# IBVG-DRIVER.net
KiCad netlist of a schematic drawn in Altium Designer
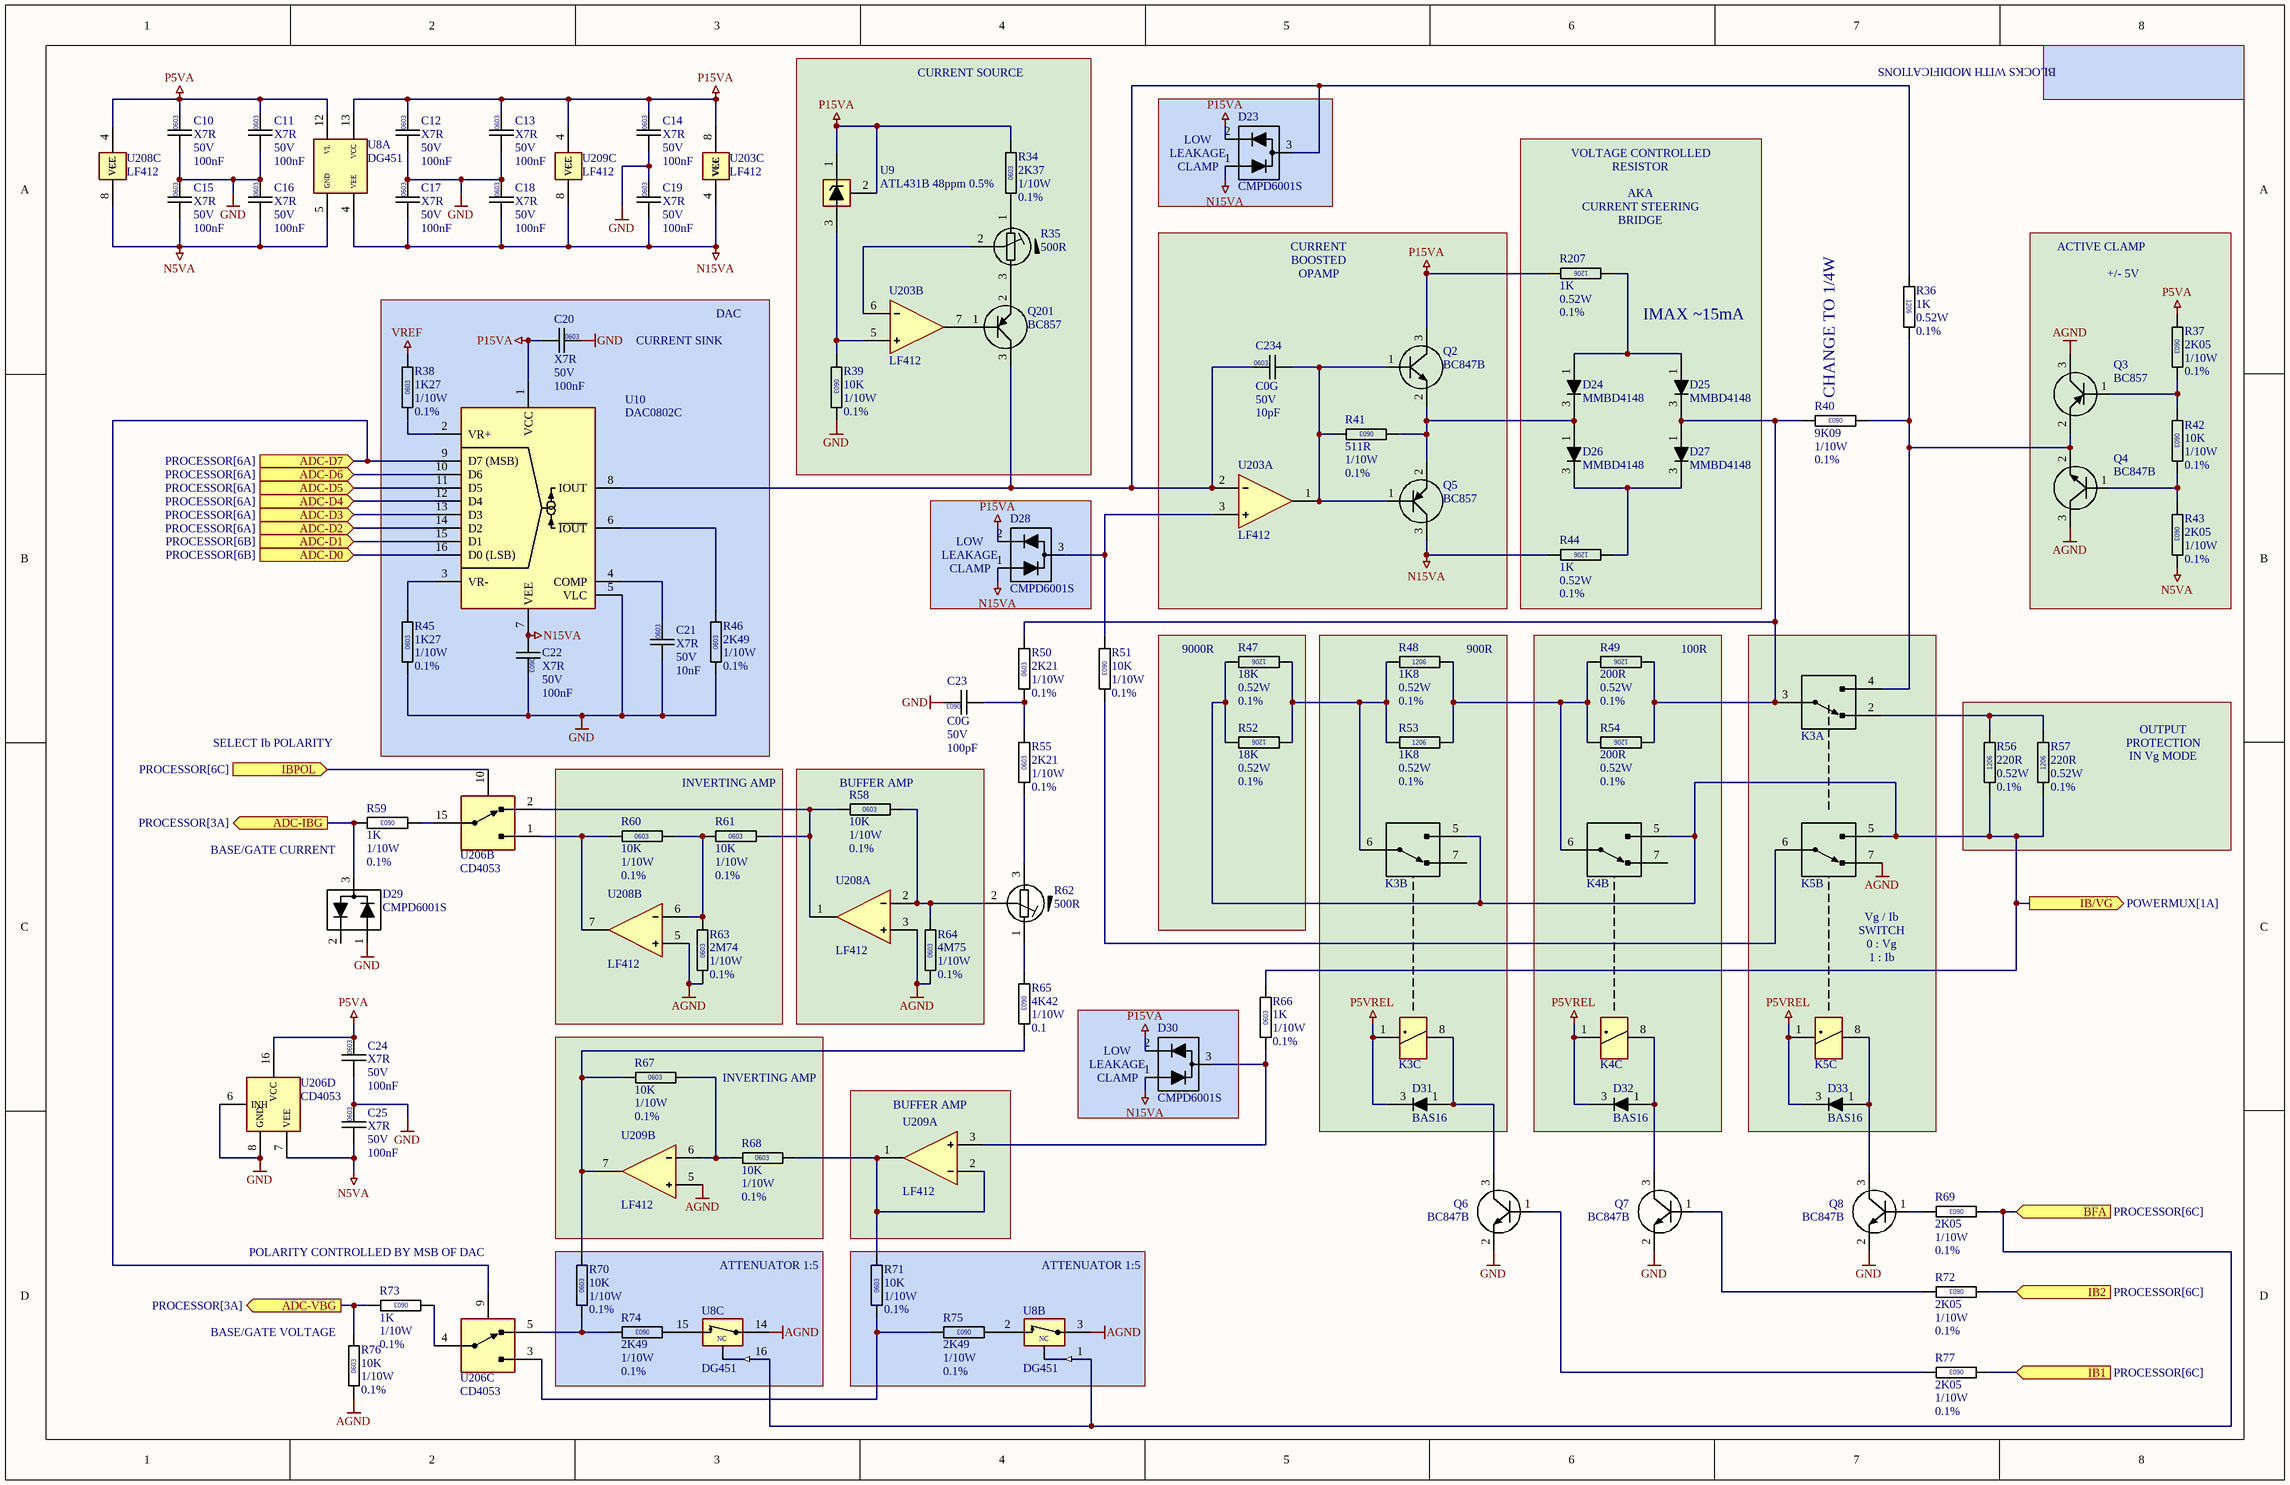
[diagram p0: IBVG-DRIVER.SchDoc]

(export (version "E")
  (design (tool "Eeschema 10.0.6"))
  (components
    (comp (ref "C10")
      (value "CAP0603")
      (footprint "CAPC0603")
      (description "CAPACITOR,CERAMIC,100nF,50V,X7R,0603")
      (fields
        (field (name "DIELECTRIC") "X7R")
        (field (name "VOLTAGE") "50V")
        (field (name "CAPACITANCE") "100nF")
      )
      (libsource (lib "CAPACITORS") (part "CAPC-0603-100nF-50V-X7R"))
    )
    (comp (ref "C11")
      (value "CAP0603")
      (footprint "CAPC0603")
      (description "CAPACITOR,CERAMIC,100nF,50V,X7R,0603")
      (fields
        (field (name "DIELECTRIC") "X7R")
        (field (name "VOLTAGE") "50V")
        (field (name "CAPACITANCE") "100nF")
      )
      (libsource (lib "CAPACITORS") (part "CAPC-0603-100nF-50V-X7R"))
    )
    (comp (ref "C12")
      (value "CAP0603")
      (footprint "CAPC0603")
      (description "CAPACITOR,CERAMIC,100nF,50V,X7R,0603")
      (fields
        (field (name "DIELECTRIC") "X7R")
        (field (name "VOLTAGE") "50V")
        (field (name "CAPACITANCE") "100nF")
      )
      (libsource (lib "CAPACITORS") (part "CAPC-0603-100nF-50V-X7R"))
    )
    (comp (ref "C13")
      (value "CAP0603")
      (footprint "CAPC0603")
      (description "CAPACITOR,CERAMIC,100nF,50V,X7R,0603")
      (fields
        (field (name "DIELECTRIC") "X7R")
        (field (name "VOLTAGE") "50V")
        (field (name "CAPACITANCE") "100nF")
      )
      (libsource (lib "CAPACITORS") (part "CAPC-0603-100nF-50V-X7R"))
    )
    (comp (ref "C14")
      (value "CAP0603")
      (footprint "CAPC0603")
      (description "CAPACITOR,CERAMIC,100nF,50V,X7R,0603")
      (fields
        (field (name "DIELECTRIC") "X7R")
        (field (name "VOLTAGE") "50V")
        (field (name "CAPACITANCE") "100nF")
      )
      (libsource (lib "CAPACITORS") (part "CAPC-0603-100nF-50V-X7R"))
    )
    (comp (ref "C15")
      (value "CAP0603")
      (footprint "CAPC0603")
      (description "CAPACITOR,CERAMIC,100nF,50V,X7R,0603")
      (fields
        (field (name "DIELECTRIC") "X7R")
        (field (name "VOLTAGE") "50V")
        (field (name "CAPACITANCE") "100nF")
      )
      (libsource (lib "CAPACITORS") (part "CAPC-0603-100nF-50V-X7R"))
    )
    (comp (ref "C16")
      (value "CAP0603")
      (footprint "CAPC0603")
      (description "CAPACITOR,CERAMIC,100nF,50V,X7R,0603")
      (fields
        (field (name "DIELECTRIC") "X7R")
        (field (name "VOLTAGE") "50V")
        (field (name "CAPACITANCE") "100nF")
      )
      (libsource (lib "CAPACITORS") (part "CAPC-0603-100nF-50V-X7R"))
    )
    (comp (ref "C17")
      (value "CAP0603")
      (footprint "CAPC0603")
      (description "CAPACITOR,CERAMIC,100nF,50V,X7R,0603")
      (fields
        (field (name "DIELECTRIC") "X7R")
        (field (name "VOLTAGE") "50V")
        (field (name "CAPACITANCE") "100nF")
      )
      (libsource (lib "CAPACITORS") (part "CAPC-0603-100nF-50V-X7R"))
    )
    (comp (ref "C18")
      (value "CAP0603")
      (footprint "CAPC0603")
      (description "CAPACITOR,CERAMIC,100nF,50V,X7R,0603")
      (fields
        (field (name "DIELECTRIC") "X7R")
        (field (name "VOLTAGE") "50V")
        (field (name "CAPACITANCE") "100nF")
      )
      (libsource (lib "CAPACITORS") (part "CAPC-0603-100nF-50V-X7R"))
    )
    (comp (ref "C19")
      (value "CAP0603")
      (footprint "CAPC0603")
      (description "CAPACITOR,CERAMIC,100nF,50V,X7R,0603")
      (fields
        (field (name "DIELECTRIC") "X7R")
        (field (name "VOLTAGE") "50V")
        (field (name "CAPACITANCE") "100nF")
      )
      (libsource (lib "CAPACITORS") (part "CAPC-0603-100nF-50V-X7R"))
    )
    (comp (ref "C20")
      (value "CAP0603")
      (footprint "CAPC0603")
      (description "CAPACITOR,CERAMIC,100nF,50V,X7R,0603")
      (fields
        (field (name "DIELECTRIC") "X7R")
        (field (name "VOLTAGE") "50V")
        (field (name "CAPACITANCE") "100nF")
      )
      (libsource (lib "CAPACITORS") (part "CAPC-0603-100nF-50V-X7R"))
    )
    (comp (ref "C21")
      (value "CAP0603")
      (footprint "CAPC0603")
      (description "CAPACITOR,CERAMIC,10nF,50V,X7R,0603")
      (fields
        (field (name "DIELECTRIC") "X7R")
        (field (name "VOLTAGE") "50V")
        (field (name "CAPACITANCE") "10nF")
      )
      (libsource (lib "CAPACITORS") (part "CAPC-0603-10nF-50V-X7R"))
    )
    (comp (ref "C22")
      (value "CAP0603")
      (footprint "CAPC0603")
      (description "CAPACITOR,CERAMIC,100nF,50V,X7R,0603")
      (fields
        (field (name "DIELECTRIC") "X7R")
        (field (name "VOLTAGE") "50V")
        (field (name "CAPACITANCE") "100nF")
      )
      (libsource (lib "CAPACITORS") (part "CAPC-0603-100nF-50V-X7R"))
    )
    (comp (ref "C23")
      (value "CAP0603")
      (footprint "CAPC0603")
      (description "CAPACITOR,CERAMIC,100pF,50V,C0G,0603")
      (fields
        (field (name "DIELECTRIC") "C0G")
        (field (name "VOLTAGE") "50V")
        (field (name "CAPACITANCE") "100pF")
      )
      (libsource (lib "CAPACITORS") (part "CAPC-0603-100pF-50V-C0G"))
    )
    (comp (ref "C24")
      (value "CAP0603")
      (footprint "CAPC0603")
      (description "CAPACITOR,CERAMIC,100nF,50V,X7R,0603")
      (fields
        (field (name "DIELECTRIC") "X7R")
        (field (name "VOLTAGE") "50V")
        (field (name "CAPACITANCE") "100nF")
      )
      (libsource (lib "CAPACITORS") (part "CAPC-0603-100nF-50V-X7R"))
    )
    (comp (ref "C25")
      (value "CAP0603")
      (footprint "CAPC0603")
      (description "CAPACITOR,CERAMIC,100nF,50V,X7R,0603")
      (fields
        (field (name "DIELECTRIC") "X7R")
        (field (name "VOLTAGE") "50V")
        (field (name "CAPACITANCE") "100nF")
      )
      (libsource (lib "CAPACITORS") (part "CAPC-0603-100nF-50V-X7R"))
    )
    (comp (ref "C234")
      (value "CAP0603")
      (footprint "CAPC0603")
      (description "CAPACITOR,CERAMIC,10pF,50V,C0G,0603")
      (fields
        (field (name "DIELECTRIC") "C0G")
        (field (name "VOLTAGE") "50V")
        (field (name "CAPACITANCE") "10pF")
      )
      (libsource (lib "CAPACITORS") (part "CAPC-0603-10PF-50V-C0G"))
    )
    (comp (ref "D23")
      (value "CMPD6001S")
      (footprint "SOT23")
      (description "DIODE,75V,250mA,SOT23,500pA ULTRA LOW LEAKAGE")
      (libsource (lib "DIODES") (part "DIODE-CENTRALSEMI-CMPD6001S"))
    )
    (comp (ref "D24")
      (value "MMBD4148")
      (description "DIODE,RECTIFIER,75V,0.3A,MMBD4148,SOT23")
      (libsource (lib "DIODES") (part "DIODE-RECTIFIER-DIODES-MMBD4148-SOT23"))
    )
    (comp (ref "D25")
      (value "MMBD4148")
      (description "DIODE,RECTIFIER,75V,0.3A,MMBD4148,SOT23")
      (libsource (lib "DIODES") (part "DIODE-RECTIFIER-DIODES-MMBD4148-SOT23"))
    )
    (comp (ref "D26")
      (value "MMBD4148")
      (description "DIODE,RECTIFIER,75V,0.3A,MMBD4148,SOT23")
      (libsource (lib "DIODES") (part "DIODE-RECTIFIER-DIODES-MMBD4148-SOT23"))
    )
    (comp (ref "D27")
      (value "MMBD4148")
      (description "DIODE,RECTIFIER,75V,0.3A,MMBD4148,SOT23")
      (libsource (lib "DIODES") (part "DIODE-RECTIFIER-DIODES-MMBD4148-SOT23"))
    )
    (comp (ref "D28")
      (value "CMPD6001S")
      (footprint "SOT23")
      (description "DIODE,75V,250mA,SOT23,500pA ULTRA LOW LEAKAGE")
      (libsource (lib "DIODES") (part "DIODE-CENTRALSEMI-CMPD6001S"))
    )
    (comp (ref "D29")
      (value "CMPD6001S")
      (footprint "SOT23")
      (description "DIODE,75V,250mA,SOT23,500pA ULTRA LOW LEAKAGE")
      (libsource (lib "DIODES") (part "DIODE-CENTRALSEMI-CMPD6001S"))
    )
    (comp (ref "D30")
      (value "CMPD6001S")
      (footprint "SOT23")
      (description "DIODE,75V,250mA,SOT23,500pA ULTRA LOW LEAKAGE")
      (libsource (lib "DIODES") (part "DIODE-CENTRALSEMI-CMPD6001S"))
    )
    (comp (ref "D31")
      (value "BAS16")
      (footprint "SOT23")
      (description "DIODE,RECTIFIER,75V,0.3A,BAS16,SOT23")
      (libsource (lib "DIODES") (part "DIODE-RECTIFIER-DIODES-BAS16-SOT23"))
    )
    (comp (ref "D32")
      (value "BAS16")
      (footprint "SOT23")
      (description "DIODE,RECTIFIER,75V,0.3A,BAS16,SOT23")
      (libsource (lib "DIODES") (part "DIODE-RECTIFIER-DIODES-BAS16-SOT23"))
    )
    (comp (ref "D33")
      (value "BAS16")
      (footprint "SOT23")
      (description "DIODE,RECTIFIER,75V,0.3A,BAS16,SOT23")
      (libsource (lib "DIODES") (part "DIODE-RECTIFIER-DIODES-BAS16-SOT23"))
    )
    (comp (ref "K3")
      (value "RELAY-KEMET-UA2-5NJ")
      (footprint "RELAY-KEMET-UA2-5NJ")
      (description "RELAY,DPDT,1A,250VAC,220VDC,5V COIL,KEMET,UA2-5NJ")
      (libsource (lib "") (part "RELAY-KEMET-UA2-5NJ_1"))
    )
    (comp (ref "K4")
      (value "RELAY-KEMET-UA2-5NJ")
      (footprint "RELAY-KEMET-UA2-5NJ")
      (description "RELAY,DPDT,1A,250VAC,220VDC,5V COIL,KEMET,UA2-5NJ")
      (libsource (lib "RELAYS") (part "RELAY-KEMET-UA2-5NJ"))
    )
    (comp (ref "K5")
      (value "RELAY-KEMET-UA2-5NJ")
      (footprint "RELAY-KEMET-UA2-5NJ")
      (description "RELAY,DPDT,1A,250VAC,220VDC,5V COIL,KEMET,UA2-5NJ")
      (libsource (lib "RELAYS") (part "RELAY-KEMET-UA2-5NJ"))
    )
    (comp (ref "Q2")
      (value "BC847B")
      (footprint "SOT23")
      (description "XSTR,NPN,45V,0.1A,,BC847B,SOT23")
      (libsource (lib "TRANSISTORS") (part "XSTR-NPN-BC847"))
    )
    (comp (ref "Q3")
      (value "BC857")
      (footprint "SOT23")
      (description "XSTR,PNP,SOT23,BC857,SOT23")
      (libsource (lib "TRANSISTORS") (part "XSTR-PNP-BC857"))
    )
    (comp (ref "Q4")
      (value "BC847B")
      (footprint "SOT23")
      (description "XSTR,NPN,45V,0.1A,,BC847B,SOT23")
      (libsource (lib "TRANSISTORS") (part "XSTR-NPN-BC847"))
    )
    (comp (ref "Q5")
      (value "BC857")
      (footprint "SOT23")
      (description "XSTR,PNP,SOT23,BC857,SOT23")
      (libsource (lib "TRANSISTORS") (part "XSTR-PNP-BC857"))
    )
    (comp (ref "Q6")
      (value "BC847B")
      (footprint "SOT23")
      (description "XSTR,NPN,45V,0.1A,,BC847B,SOT23")
      (libsource (lib "TRANSISTORS") (part "XSTR-NPN-BC847"))
    )
    (comp (ref "Q7")
      (value "BC847B")
      (footprint "SOT23")
      (description "XSTR,NPN,45V,0.1A,,BC847B,SOT23")
      (libsource (lib "TRANSISTORS") (part "XSTR-NPN-BC847"))
    )
    (comp (ref "Q8")
      (value "BC847B")
      (footprint "SOT23")
      (description "XSTR,NPN,45V,0.1A,,BC847B,SOT23")
      (libsource (lib "TRANSISTORS") (part "XSTR-NPN-BC847"))
    )
    (comp (ref "Q201")
      (value "BC857")
      (footprint "SOT23")
      (description "XSTR,PNP,SOT23,BC857,SOT23")
      (libsource (lib "TRANSISTORS") (part "XSTR-PNP-BC857"))
    )
    (comp (ref "R34")
      (value "2K37")
      (footprint "RESC0603")
      (description "RESISTOR,2K37,0.1%,100mW,0603 (1608)")
      (fields
        (field (name "POWER") "1/10W")
        (field (name "TOLERANCE") "0.1%")
        (field (name "Comment") "RESC0603")
      )
      (libsource (lib "RESISTORS") (part "RESC-0603-2K37-0.1%-1/10W"))
    )
    (comp (ref "R35")
      (value "500R")
      (footprint "TRIMMER-BOURNS-3214X")
      (description "RESISTOR,MULTITURN,VERTICAL,5T,500R")
      (fields (field (name "Comment") "TRIMMER-BOURNS-3214X-1-501"))
      (libsource (lib "RESISTORS") (part "TRIMMER-BOURNS-3214X-1-501"))
    )
    (comp (ref "R36")
      (value "1K")
      (footprint "RESC1206")
      (description "RESISTOR,1K,1206,0.1%,520mW,1206")
      (fields
        (field (name "POWER") "0.52W")
        (field (name "TOLERANCE") "0.1%")
        (field (name "Comment") "RESC1206")
      )
      (libsource (lib "RESISTORS") (part "RESC-1206-1K-0.1%-1/2W"))
    )
    (comp (ref "R37")
      (value "2K05")
      (footprint "RESC0603")
      (description "RESISTOR,2K05,0.11%,100mW,0603 (1608)")
      (fields
        (field (name "POWER") "1/10W")
        (field (name "TOLERANCE") "0.1%")
        (field (name "Comment") "RESC0603")
      )
      (libsource (lib "RESISTORS") (part "RESC-0603-2K05-0.1%-1/10W"))
    )
    (comp (ref "R38")
      (value "1K27")
      (footprint "RESC0603")
      (description "RESISTOR,1K27,0.1%,100mW,0603 (1608)")
      (fields
        (field (name "POWER") "1/10W")
        (field (name "TOLERANCE") "0.1%")
        (field (name "Comment") "RESC0603")
      )
      (libsource (lib "RESISTORS") (part "RESC-0603-1K27-0.1%-1/10W"))
    )
    (comp (ref "R39")
      (value "10K")
      (footprint "RESC0603")
      (description "RESISTOR,10K,0.1%,100mW,0603 (1608)")
      (fields
        (field (name "POWER") "1/10W")
        (field (name "TOLERANCE") "0.1%")
        (field (name "Comment") "RESC0603")
      )
      (libsource (lib "RESISTORS") (part "RESC-0603-10K-0.1%-1/10W"))
    )
    (comp (ref "R40")
      (value "9K09")
      (footprint "RESC0603")
      (description "RESISTOR,9K09,0.1%,100mW,0603 (1608)")
      (fields
        (field (name "POWER") "1/10W")
        (field (name "TOLERANCE") "0.1%")
        (field (name "Comment") "RESC0603")
      )
      (libsource (lib "RESISTORS") (part "RESC-0603-9K09-0.1%-1/10W"))
    )
    (comp (ref "R41")
      (value "511R")
      (footprint "RESC0603")
      (description "RESISTOR,511R,0.1%,100mW,0603 (1608)")
      (fields
        (field (name "POWER") "1/10W")
        (field (name "TOLERANCE") "0.1%")
        (field (name "Comment") "RESC0603")
      )
      (libsource (lib "RESISTORS") (part "RESC-0603-511R-0.1%-1/10W"))
    )
    (comp (ref "R42")
      (value "10K")
      (footprint "RESC0603")
      (description "RESISTOR,10K,0.1%,100mW,0603 (1608)")
      (fields
        (field (name "POWER") "1/10W")
        (field (name "TOLERANCE") "0.1%")
        (field (name "Comment") "RESC0603")
      )
      (libsource (lib "RESISTORS") (part "RESC-0603-10K-0.1%-1/10W"))
    )
    (comp (ref "R43")
      (value "2K05")
      (footprint "RESC0603")
      (description "RESISTOR,2K05,0.11%,100mW,0603 (1608)")
      (fields
        (field (name "POWER") "1/10W")
        (field (name "TOLERANCE") "0.1%")
        (field (name "Comment") "RESC0603")
      )
      (libsource (lib "RESISTORS") (part "RESC-0603-2K05-0.1%-1/10W"))
    )
    (comp (ref "R44")
      (value "1K")
      (footprint "RESC1206")
      (description "RESISTOR,1K,1206,0.1%,520mW,1206")
      (fields
        (field (name "POWER") "0.52W")
        (field (name "TOLERANCE") "0.1%")
        (field (name "Comment") "RESC1206")
      )
      (libsource (lib "RESISTORS") (part "RESC-1206-1K-0.1%-1/2W"))
    )
    (comp (ref "R45")
      (value "1K27")
      (footprint "RESC0603")
      (description "RESISTOR,1K27,0.1%,100mW,0603 (1608)")
      (fields
        (field (name "POWER") "1/10W")
        (field (name "TOLERANCE") "0.1%")
        (field (name "Comment") "RESC0603")
      )
      (libsource (lib "RESISTORS") (part "RESC-0603-1K27-0.1%-1/10W"))
    )
    (comp (ref "R46")
      (value "2K49")
      (footprint "RESC0603")
      (description "RESISTOR,2K49,0.1%,100mW,0603 (1608)")
      (fields
        (field (name "POWER") "1/10W")
        (field (name "TOLERANCE") "0.1%")
        (field (name "Comment") "RESC0603")
      )
      (libsource (lib "RESISTORS") (part "RESC-0603-2K49-0.1%-1/10W"))
    )
    (comp (ref "R47")
      (value "18K")
      (footprint "RESC1206")
      (description "RESISTOR,18K,1206,0.1%,520mW,1206")
      (fields
        (field (name "POWER") "0.52W")
        (field (name "TOLERANCE") "0.1%")
        (field (name "Comment") "RESC1206")
      )
      (libsource (lib "RESISTORS") (part "RESC-1206-18K-0.1%-1/2W"))
    )
    (comp (ref "R48")
      (value "1K8")
      (footprint "RESC1206")
      (description "RESISTOR,1K8,1206,0.1%,520mW,1206")
      (fields
        (field (name "POWER") "0.52W")
        (field (name "TOLERANCE") "0.1%")
        (field (name "Comment") "RESC1206")
      )
      (libsource (lib "RESISTORS") (part "RESC-1206-1K8-0.1%-1/2W"))
    )
    (comp (ref "R49")
      (value "200R")
      (footprint "RESC1206")
      (description "RESISTOR,200R,1206,0.1%,520mW,1206")
      (fields
        (field (name "POWER") "0.52W")
        (field (name "TOLERANCE") "0.1%")
        (field (name "Comment") "RESC1206")
      )
      (libsource (lib "RESISTORS") (part "RESC-1206-200R-0.1%-1/2W"))
    )
    (comp (ref "R50")
      (value "2K21")
      (footprint "RESC0603")
      (description "RESISTOR,2K21,0.1%,100mW,0603 (1608)")
      (fields
        (field (name "POWER") "1/10W")
        (field (name "TOLERANCE") "0.1%")
        (field (name "Comment") "RESC0603")
      )
      (libsource (lib "RESISTORS") (part "RESC-0603-2K21-0.1%-1/10W"))
    )
    (comp (ref "R51")
      (value "10K")
      (footprint "RESC0603")
      (description "RESISTOR,10K,0.1%,100mW,0603 (1608)")
      (fields
        (field (name "POWER") "1/10W")
        (field (name "TOLERANCE") "0.1%")
        (field (name "Comment") "RESC0603")
      )
      (libsource (lib "RESISTORS") (part "RESC-0603-10K-0.1%-1/10W"))
    )
    (comp (ref "R52")
      (value "18K")
      (footprint "RESC1206")
      (description "RESISTOR,18K,1206,0.1%,520mW,1206")
      (fields
        (field (name "POWER") "0.52W")
        (field (name "TOLERANCE") "0.1%")
        (field (name "Comment") "RESC1206")
      )
      (libsource (lib "RESISTORS") (part "RESC-1206-18K-0.1%-1/2W"))
    )
    (comp (ref "R53")
      (value "1K8")
      (footprint "RESC1206")
      (description "RESISTOR,1K8,1206,0.1%,520mW,1206")
      (fields
        (field (name "POWER") "0.52W")
        (field (name "TOLERANCE") "0.1%")
        (field (name "Comment") "RESC1206")
      )
      (libsource (lib "RESISTORS") (part "RESC-1206-1K8-0.1%-1/2W"))
    )
    (comp (ref "R54")
      (value "200R")
      (footprint "RESC1206")
      (description "RESISTOR,200R,1206,0.1%,520mW,1206")
      (fields
        (field (name "POWER") "0.52W")
        (field (name "TOLERANCE") "0.1%")
        (field (name "Comment") "RESC1206")
      )
      (libsource (lib "RESISTORS") (part "RESC-1206-200R-0.1%-1/2W"))
    )
    (comp (ref "R55")
      (value "2K21")
      (footprint "RESC0603")
      (description "RESISTOR,2K21,0.1%,100mW,0603 (1608)")
      (fields
        (field (name "POWER") "1/10W")
        (field (name "TOLERANCE") "0.1%")
        (field (name "Comment") "RESC0603")
      )
      (libsource (lib "RESISTORS") (part "RESC-0603-2K21-0.1%-1/10W"))
    )
    (comp (ref "R56")
      (value "220R")
      (footprint "RESC1206")
      (description "RESISTOR,220R,1206,0.1%,520mW,1206")
      (fields
        (field (name "POWER") "0.52W")
        (field (name "TOLERANCE") "0.1%")
        (field (name "Comment") "RESC1206")
      )
      (libsource (lib "RESISTORS") (part "RESC-1206-220R-0.1%-1/2W"))
    )
    (comp (ref "R57")
      (value "220R")
      (footprint "RESC1206")
      (description "RESISTOR,220R,1206,0.1%,520mW,1206")
      (fields
        (field (name "POWER") "0.52W")
        (field (name "TOLERANCE") "0.1%")
        (field (name "Comment") "RESC1206")
      )
      (libsource (lib "RESISTORS") (part "RESC-1206-220R-0.1%-1/2W"))
    )
    (comp (ref "R58")
      (value "10K")
      (footprint "RESC0603")
      (description "RESISTOR,10K,0.1%,100mW,0603 (1608)")
      (fields
        (field (name "POWER") "1/10W")
        (field (name "TOLERANCE") "0.1%")
        (field (name "Comment") "RESC0603")
      )
      (libsource (lib "RESISTORS") (part "RESC-0603-10K-0.1%-1/10W"))
    )
    (comp (ref "R59")
      (value "1K")
      (footprint "RESC0603")
      (description "RESISTOR,1K,0.1%,100mW,0603 (1608)")
      (fields
        (field (name "POWER") "1/10W")
        (field (name "TOLERANCE") "0.1%")
        (field (name "Comment") "RESC0603")
      )
      (libsource (lib "RESISTORS") (part "RESC-0603-1K-0.1%-1/10W"))
    )
    (comp (ref "R60")
      (value "10K")
      (footprint "RESC0603")
      (description "RESISTOR,10K,0.1%,100mW,0603 (1608)")
      (fields
        (field (name "POWER") "1/10W")
        (field (name "TOLERANCE") "0.1%")
        (field (name "Comment") "RESC0603")
      )
      (libsource (lib "RESISTORS") (part "RESC-0603-10K-0.1%-1/10W"))
    )
    (comp (ref "R61")
      (value "10K")
      (footprint "RESC0603")
      (description "RESISTOR,10K,0.1%,100mW,0603 (1608)")
      (fields
        (field (name "POWER") "1/10W")
        (field (name "TOLERANCE") "0.1%")
        (field (name "Comment") "RESC0603")
      )
      (libsource (lib "RESISTORS") (part "RESC-0603-10K-0.1%-1/10W"))
    )
    (comp (ref "R62")
      (value "500R")
      (footprint "TRIMMER-BOURNS-3214X")
      (description "RESISTOR,MULTITURN,VERTICAL,5T,500R")
      (fields (field (name "Comment") "TRIMMER-BOURNS-3214X-1-501"))
      (libsource (lib "RESISTORS") (part "TRIMMER-BOURNS-3214X-1-501"))
    )
    (comp (ref "R63")
      (value "2M74")
      (footprint "RESC0603")
      (description "RESISTOR,2M74,0.1%,100mW,0603 (1608)")
      (fields
        (field (name "POWER") "1/10W")
        (field (name "TOLERANCE") "0.1%")
        (field (name "Comment") "RESC0603")
      )
      (libsource (lib "RESISTORS") (part "RESC-0603-2M74-0.1%-1/10W"))
    )
    (comp (ref "R64")
      (value "4M75")
      (footprint "RESC0603")
      (description "RESISTOR,4M75,0.1%,100mW,0603 (1608)")
      (fields
        (field (name "POWER") "1/10W")
        (field (name "TOLERANCE") "0.1%")
        (field (name "Comment") "RESC0603")
      )
      (libsource (lib "RESISTORS") (part "RESC-0603-4M75-1%-1/10W"))
    )
    (comp (ref "R65")
      (value "4K42")
      (footprint "RESC0603")
      (description "RESISTOR,4K42,0.1%,100mW,0603 (1608)")
      (fields
        (field (name "POWER") "1/10W")
        (field (name "TOLERANCE") "0.1")
        (field (name "Comment") "RESC0603")
      )
      (libsource (lib "RESISTORS") (part "RESC-0603-4K42-0.1%-1/10W"))
    )
    (comp (ref "R66")
      (value "1K")
      (footprint "RESC0603")
      (description "RESISTOR,1K,0.1%,100mW,0603 (1608)")
      (fields
        (field (name "POWER") "1/10W")
        (field (name "TOLERANCE") "0.1%")
        (field (name "Comment") "RESC0603")
      )
      (libsource (lib "RESISTORS") (part "RESC-0603-1K-0.1%-1/10W"))
    )
    (comp (ref "R67")
      (value "10K")
      (footprint "RESC0603")
      (description "RESISTOR,10K,0.1%,100mW,0603 (1608)")
      (fields
        (field (name "POWER") "1/10W")
        (field (name "TOLERANCE") "0.1%")
        (field (name "Comment") "RESC0603")
      )
      (libsource (lib "RESISTORS") (part "RESC-0603-10K-0.1%-1/10W"))
    )
    (comp (ref "R68")
      (value "10K")
      (footprint "RESC0603")
      (description "RESISTOR,10K,0.1%,100mW,0603 (1608)")
      (fields
        (field (name "POWER") "1/10W")
        (field (name "TOLERANCE") "0.1%")
        (field (name "Comment") "RESC0603")
      )
      (libsource (lib "RESISTORS") (part "RESC-0603-10K-0.1%-1/10W"))
    )
    (comp (ref "R69")
      (value "2K05")
      (footprint "RESC0603")
      (description "RESISTOR,2K05,0.11%,100mW,0603 (1608)")
      (fields
        (field (name "POWER") "1/10W")
        (field (name "TOLERANCE") "0.1%")
        (field (name "Comment") "RESC0603")
      )
      (libsource (lib "RESISTORS") (part "RESC-0603-2K05-0.1%-1/10W"))
    )
    (comp (ref "R70")
      (value "10K")
      (footprint "RESC0603")
      (description "RESISTOR,10K,0.1%,100mW,0603 (1608)")
      (fields
        (field (name "POWER") "1/10W")
        (field (name "TOLERANCE") "0.1%")
        (field (name "Comment") "RESC0603")
      )
      (libsource (lib "RESISTORS") (part "RESC-0603-10K-0.1%-1/10W"))
    )
    (comp (ref "R71")
      (value "10K")
      (footprint "RESC0603")
      (description "RESISTOR,10K,0.1%,100mW,0603 (1608)")
      (fields
        (field (name "POWER") "1/10W")
        (field (name "TOLERANCE") "0.1%")
        (field (name "Comment") "RESC0603")
      )
      (libsource (lib "RESISTORS") (part "RESC-0603-10K-0.1%-1/10W"))
    )
    (comp (ref "R72")
      (value "2K05")
      (footprint "RESC0603")
      (description "RESISTOR,2K05,0.11%,100mW,0603 (1608)")
      (fields
        (field (name "POWER") "1/10W")
        (field (name "TOLERANCE") "0.1%")
        (field (name "Comment") "RESC0603")
      )
      (libsource (lib "RESISTORS") (part "RESC-0603-2K05-0.1%-1/10W"))
    )
    (comp (ref "R73")
      (value "1K")
      (footprint "RESC0603")
      (description "RESISTOR,1K,0.1%,100mW,0603 (1608)")
      (fields
        (field (name "POWER") "1/10W")
        (field (name "TOLERANCE") "0.1%")
        (field (name "Comment") "RESC0603")
      )
      (libsource (lib "RESISTORS") (part "RESC-0603-1K-0.1%-1/10W"))
    )
    (comp (ref "R74")
      (value "2K49")
      (footprint "RESC0603")
      (description "RESISTOR,2K49,0.1%,100mW,0603 (1608)")
      (fields
        (field (name "POWER") "1/10W")
        (field (name "TOLERANCE") "0.1%")
        (field (name "Comment") "RESC0603")
      )
      (libsource (lib "RESISTORS") (part "RESC-0603-2K49-0.1%-1/10W"))
    )
    (comp (ref "R75")
      (value "2K49")
      (footprint "RESC0603")
      (description "RESISTOR,2K49,0.1%,100mW,0603 (1608)")
      (fields
        (field (name "POWER") "1/10W")
        (field (name "TOLERANCE") "0.1%")
        (field (name "Comment") "RESC0603")
      )
      (libsource (lib "RESISTORS") (part "RESC-0603-2K49-0.1%-1/10W"))
    )
    (comp (ref "R76")
      (value "10K")
      (footprint "RESC0603")
      (description "RESISTOR,10K,0.1%,100mW,0603 (1608)")
      (fields
        (field (name "POWER") "1/10W")
        (field (name "TOLERANCE") "0.1%")
        (field (name "Comment") "RESC0603")
      )
      (libsource (lib "RESISTORS") (part "RESC-0603-10K-0.1%-1/10W"))
    )
    (comp (ref "R77")
      (value "2K05")
      (footprint "RESC0603")
      (description "RESISTOR,2K05,0.11%,100mW,0603 (1608)")
      (fields
        (field (name "POWER") "1/10W")
        (field (name "TOLERANCE") "0.1%")
        (field (name "Comment") "RESC0603")
      )
      (libsource (lib "RESISTORS") (part "RESC-0603-2K05-0.1%-1/10W"))
    )
    (comp (ref "R207")
      (value "1K")
      (footprint "RESC1206")
      (description "RESISTOR,1K,1206,0.1%,520mW,1206")
      (fields
        (field (name "POWER") "0.52W")
        (field (name "TOLERANCE") "0.1%")
        (field (name "Comment") "RESC1206")
      )
      (libsource (lib "RESISTORS") (part "RESC-1206-1K-0.1%-1/2W"))
    )
    (comp (ref "U8")
      (value "DG451")
      (footprint "SO127P600-16N")
      (description "IC,ANALOG,4XSPST ANALOG SWITCH,NC,,SILICONIX,DG451,SO16")
      (libsource (lib "IC-ANALOG") (part "IC-SILICONIX-DG451"))
    )
    (comp (ref "U9")
      (value "ATL431B 48ppm 0.5%")
      (footprint "SOT23")
      (description "IC,REGULATOR,REFERENCE,SHUNT,0.5%,48ppm,TL431,SOT23")
      (libsource (lib "IC-ANALOG") (part "IC-TI-ATL431B-SOT23"))
    )
    (comp (ref "U10")
      (value "DAC0802C")
      (description "IC,DAC,8 BIT,CURRENT DIFF,TI,DAC0802LCMX/NOPB,SO16")
      (libsource (lib "IC-ADDA") (part "IC-TI-DAC0802LCMX/NOPB"))
    )
    (comp (ref "U203")
      (value "LF412")
      (footprint "SO127P600-8N")
      (description "IC,OPAMP JFET,DUAL,LF412,SO8")
      (libsource (lib "IC-OPAMP") (part "IC-TI-LF412-S08"))
    )
    (comp (ref "U206")
      (value "CD4053")
      (footprint "SO127P600-16N")
      (description "IC,LOGIC,CMOS,4XXX,TRIPLE 2:1 MUX,SPLIT BLOCKS")
      (libsource (lib "") (part "IC-TI-CD4053-SPLIT_1"))
    )
    (comp (ref "U208")
      (value "LF412")
      (footprint "SO127P600-8N")
      (description "IC,OPAMP JFET,DUAL,LF412,SO8")
      (libsource (lib "") (part "IC-TI-LF412-S08_1"))
    )
    (comp (ref "U209")
      (value "LF412")
      (footprint "SO127P600-8N")
      (description "IC,OPAMP JFET,DUAL,LF412,SO8")
      (libsource (lib "") (part "IC-TI-LF412-S08_1"))
    )
  )
  (nets
    (net (code "1") (name "/ADC-D0") (class "Default")
      (node (ref "U10") (pin "16") (pinfunction "D0_(LSB)_16") (pintype "passive"))
    )
    (net (code "2") (name "/ADC-D1") (class "Default")
      (node (ref "U10") (pin "15") (pinfunction "D1_15") (pintype "passive"))
    )
    (net (code "3") (name "/ADC-D2") (class "Default")
      (node (ref "U10") (pin "14") (pinfunction "D2_14") (pintype "passive"))
    )
    (net (code "4") (name "/ADC-D3") (class "Default")
      (node (ref "U10") (pin "13") (pinfunction "D3_13") (pintype "passive"))
    )
    (net (code "5") (name "/ADC-D4") (class "Default")
      (node (ref "U10") (pin "12") (pinfunction "D4_12") (pintype "passive"))
    )
    (net (code "6") (name "/ADC-D5") (class "Default")
      (node (ref "U10") (pin "11") (pinfunction "D5_11") (pintype "passive"))
    )
    (net (code "7") (name "/ADC-D6") (class "Default")
      (node (ref "U10") (pin "10") (pinfunction "D6_10") (pintype "passive"))
    )
    (net (code "8") (name "/ADC-D7") (class "Default")
      (node (ref "U10") (pin "9") (pinfunction "D7_(MSB)_9") (pintype "passive"))
      (node (ref "U206") (pin "9") (pinfunction "B_9") (pintype "passive"))
    )
    (net (code "9") (name "/ADC-IBG") (class "Default")
      (node (ref "D29") (pin "3") (pinfunction "A_3") (pintype "passive"))
      (node (ref "R59") (pin "1") (pintype "passive"))
    )
    (net (code "10") (name "/ADC-VBG") (class "Default")
      (node (ref "R73") (pin "1") (pintype "passive"))
      (node (ref "R76") (pin "1") (pintype "passive"))
    )
    (net (code "11") (name "/BFA") (class "Default")
      (node (ref "R69") (pin "1") (pintype "passive"))
      (node (ref "U8") (pin "1") (pinfunction "1_1") (pintype "input"))
      (node (ref "U8") (pin "16") (pinfunction "16_16") (pintype "input"))
    )
    (net (code "12") (name "/IB1") (class "Default") (node (ref "R77") (pin "1") (pintype "passive")))
    (net (code "13") (name "/IB2") (class "Default") (node (ref "R72") (pin "1") (pintype "passive")))
    (net (code "14") (name "/IBPOL") (class "Default")
      (node (ref "U206") (pin "10") (pinfunction "A_10") (pintype "passive"))
    )
    (net (code "15") (name "/IB{slash}VG") (class "Default")
      (node (ref "K3") (pin "5") (pinfunction "NO_5") (pintype "passive"))
      (node (ref "K4") (pin "5") (pinfunction "NO_5") (pintype "passive"))
      (node (ref "K5") (pin "5") (pinfunction "NO_5") (pintype "passive"))
      (node (ref "R47") (pin "2") (pintype "passive"))
      (node (ref "R52") (pin "2") (pintype "passive"))
      (node (ref "R56") (pin "2") (pintype "passive"))
      (node (ref "R57") (pin "2") (pintype "passive"))
      (node (ref "R66") (pin "1") (pintype "passive"))
    )
    (net (code "16") (name "AGND") (class "Default")
      (node (ref "K5") (pin "7") (pinfunction "NC_7") (pintype "passive"))
      (node (ref "Q3") (pin "3") (pinfunction "C_3") (pintype "passive"))
      (node (ref "Q4") (pin "3") (pinfunction "C_3") (pintype "passive"))
      (node (ref "R63") (pin "2") (pintype "passive"))
      (node (ref "R64") (pin "2") (pintype "passive"))
      (node (ref "R76") (pin "2") (pintype "passive"))
      (node (ref "U208") (pin "3") (pinfunction "+_3") (pintype "passive"))
      (node (ref "U208") (pin "5") (pinfunction "+_5") (pintype "passive"))
      (node (ref "U209") (pin "5") (pinfunction "+_5") (pintype "passive"))
      (node (ref "U8") (pin "14") (pinfunction "14_14") (pintype "passive"))
      (node (ref "U8") (pin "3") (pinfunction "3_3") (pintype "passive"))
    )
    (net (code "17") (name "GND") (class "Default")
      (node (ref "C10") (pin "2") (pintype "passive"))
      (node (ref "C11") (pin "2") (pintype "passive"))
      (node (ref "C12") (pin "2") (pintype "passive"))
      (node (ref "C13") (pin "2") (pintype "passive"))
      (node (ref "C14") (pin "2") (pintype "passive"))
      (node (ref "C15") (pin "1") (pintype "passive"))
      (node (ref "C16") (pin "1") (pintype "passive"))
      (node (ref "C17") (pin "1") (pintype "passive"))
      (node (ref "C18") (pin "1") (pintype "passive"))
      (node (ref "C19") (pin "1") (pintype "passive"))
      (node (ref "C20") (pin "1") (pintype "passive"))
      (node (ref "C21") (pin "2") (pintype "passive"))
      (node (ref "C22") (pin "1") (pintype "passive"))
      (node (ref "C23") (pin "1") (pintype "passive"))
      (node (ref "C24") (pin "2") (pintype "passive"))
      (node (ref "C25") (pin "1") (pintype "passive"))
      (node (ref "D29") (pin "1") (pinfunction "K_1") (pintype "passive"))
      (node (ref "Q6") (pin "2") (pinfunction "E_2") (pintype "passive"))
      (node (ref "Q7") (pin "2") (pinfunction "E_2") (pintype "passive"))
      (node (ref "Q8") (pin "2") (pinfunction "E_2") (pintype "passive"))
      (node (ref "R39") (pin "1") (pintype "passive"))
      (node (ref "R45") (pin "2") (pintype "passive"))
      (node (ref "R46") (pin "2") (pintype "passive"))
      (node (ref "U10") (pin "5") (pinfunction "VLC_5") (pintype "passive"))
      (node (ref "U206") (pin "6") (pinfunction "INH_6") (pintype "passive"))
      (node (ref "U206") (pin "8") (pinfunction "GND_8") (pintype "passive"))
    )
    (net (code "18") (name "N5VA") (class "Default")
      (node (ref "C15") (pin "2") (pintype "passive"))
      (node (ref "C16") (pin "2") (pintype "passive"))
      (node (ref "C25") (pin "2") (pintype "passive"))
      (node (ref "R43") (pin "2") (pintype "passive"))
      (node (ref "U206") (pin "7") (pinfunction "VEE_7") (pintype "passive"))
      (node (ref "U208") (pin "8") (pinfunction "VCC_8") (pintype "passive"))
      (node (ref "U8") (pin "5") (pinfunction "GND_5") (pintype "power_in"))
    )
    (net (code "19") (name "N15VA") (class "Default")
      (node (ref "C17") (pin "2") (pintype "passive"))
      (node (ref "C18") (pin "2") (pintype "passive"))
      (node (ref "C19") (pin "2") (pintype "passive"))
      (node (ref "C22") (pin "2") (pintype "passive"))
      (node (ref "D23") (pin "1") (pinfunction "K_1") (pintype "passive"))
      (node (ref "D28") (pin "1") (pinfunction "K_1") (pintype "passive"))
      (node (ref "D30") (pin "1") (pinfunction "K_1") (pintype "passive"))
      (node (ref "Q5") (pin "3") (pinfunction "C_3") (pintype "passive"))
      (node (ref "R44") (pin "1") (pintype "passive"))
      (node (ref "U10") (pin "7") (pinfunction "VEE_7") (pintype "passive"))
      (node (ref "U203") (pin "4") (pinfunction "VEE_4") (pintype "passive"))
      (node (ref "U209") (pin "8") (pinfunction "VCC_8") (pintype "passive"))
      (node (ref "U8") (pin "4") (pinfunction "VEE_4") (pintype "power_in"))
    )
    (net (code "20") (name "Net-(C23-Pad2)") (class "Default")
      (node (ref "C23") (pin "2") (pintype "passive"))
      (node (ref "R50") (pin "2") (pintype "passive"))
      (node (ref "R55") (pin "1") (pintype "passive"))
    )
    (net (code "21") (name "Net-(D24-A)") (class "Default")
      (node (ref "D24") (pin "1") (pinfunction "A_1") (pintype "passive"))
      (node (ref "D25") (pin "1") (pinfunction "A_1") (pintype "passive"))
      (node (ref "R207") (pin "2") (pintype "passive"))
    )
    (net (code "22") (name "Net-(D24-K)") (class "Default")
      (node (ref "D24") (pin "3") (pinfunction "K_3") (pintype "passive"))
      (node (ref "D26") (pin "1") (pinfunction "A_1") (pintype "passive"))
      (node (ref "Q2") (pin "2") (pinfunction "E_2") (pintype "passive"))
      (node (ref "Q5") (pin "2") (pinfunction "E_2") (pintype "passive"))
      (node (ref "R41") (pin "2") (pintype "passive"))
    )
    (net (code "23") (name "Net-(D25-K)") (class "Default")
      (node (ref "D25") (pin "3") (pinfunction "K_3") (pintype "passive"))
      (node (ref "D27") (pin "1") (pinfunction "A_1") (pintype "passive"))
      (node (ref "K3") (pin "3") (pinfunction "COM_3") (pintype "passive"))
      (node (ref "R40") (pin "1") (pintype "passive"))
      (node (ref "R49") (pin "1") (pintype "passive"))
      (node (ref "R50") (pin "1") (pintype "passive"))
      (node (ref "R54") (pin "1") (pintype "passive"))
    )
    (net (code "24") (name "Net-(D26-K)") (class "Default")
      (node (ref "D26") (pin "3") (pinfunction "K_3") (pintype "passive"))
      (node (ref "D27") (pin "3") (pinfunction "K_3") (pintype "passive"))
      (node (ref "R44") (pin "2") (pintype "passive"))
    )
    (net (code "25") (name "Net-(D31-A)") (class "Default")
      (node (ref "D31") (pin "1") (pinfunction "A_1") (pintype "passive"))
      (node (ref "K3") (pin "8") (pinfunction "8_8") (pintype "passive"))
      (node (ref "Q6") (pin "3") (pinfunction "C_3") (pintype "passive"))
    )
    (net (code "26") (name "Net-(D32-A)") (class "Default")
      (node (ref "D32") (pin "1") (pinfunction "A_1") (pintype "passive"))
      (node (ref "K4") (pin "8") (pinfunction "8_8") (pintype "passive"))
      (node (ref "Q7") (pin "3") (pinfunction "C_3") (pintype "passive"))
    )
    (net (code "27") (name "Net-(D33-A)") (class "Default")
      (node (ref "D33") (pin "1") (pinfunction "A_1") (pintype "passive"))
      (node (ref "K5") (pin "8") (pinfunction "8_8") (pintype "passive"))
      (node (ref "Q8") (pin "3") (pinfunction "C_3") (pintype "passive"))
    )
    (net (code "28") (name "Net-(K3A-NC)") (class "Default")
      (node (ref "K3") (pin "2") (pinfunction "NC_2") (pintype "passive"))
      (node (ref "R56") (pin "1") (pintype "passive"))
      (node (ref "R57") (pin "1") (pintype "passive"))
    )
    (net (code "29") (name "Net-(K3A-NO)") (class "Default")
      (node (ref "K3") (pin "4") (pinfunction "NO_4") (pintype "passive"))
      (node (ref "Q3") (pin "2") (pinfunction "E_2") (pintype "passive"))
      (node (ref "Q4") (pin "2") (pinfunction "E_2") (pintype "passive"))
      (node (ref "R36") (pin "1") (pintype "passive"))
      (node (ref "R40") (pin "2") (pintype "passive"))
    )
    (net (code "30") (name "Net-(K3B-COM)") (class "Default")
      (node (ref "K3") (pin "6") (pinfunction "COM_6") (pintype "passive"))
      (node (ref "R47") (pin "1") (pintype "passive"))
      (node (ref "R48") (pin "1") (pintype "passive"))
      (node (ref "R52") (pin "1") (pintype "passive"))
      (node (ref "R53") (pin "1") (pintype "passive"))
    )
    (net (code "31") (name "Net-(K4B-COM)") (class "Default")
      (node (ref "K4") (pin "6") (pinfunction "COM_6") (pintype "passive"))
      (node (ref "R48") (pin "2") (pintype "passive"))
      (node (ref "R49") (pin "2") (pintype "passive"))
      (node (ref "R53") (pin "2") (pintype "passive"))
      (node (ref "R54") (pin "2") (pintype "passive"))
    )
    (net (code "32") (name "Net-(K5B-COM)") (class "Default")
      (node (ref "K5") (pin "6") (pinfunction "COM_6") (pintype "passive"))
      (node (ref "R51") (pin "1") (pintype "passive"))
    )
    (net (code "33") (name "Net-(Q2-B)") (class "Default")
      (node (ref "C234") (pin "2") (pintype "passive"))
      (node (ref "Q2") (pin "1") (pinfunction "B_1") (pintype "passive"))
      (node (ref "Q5") (pin "1") (pinfunction "B_1") (pintype "passive"))
      (node (ref "R41") (pin "1") (pintype "passive"))
      (node (ref "U203") (pin "1") (pinfunction "O_1") (pintype "passive"))
    )
    (net (code "34") (name "Net-(Q3-B)") (class "Default")
      (node (ref "Q3") (pin "1") (pinfunction "B_1") (pintype "passive"))
      (node (ref "R37") (pin "2") (pintype "passive"))
      (node (ref "R42") (pin "2") (pintype "passive"))
    )
    (net (code "35") (name "Net-(Q4-B)") (class "Default")
      (node (ref "Q4") (pin "1") (pinfunction "B_1") (pintype "passive"))
      (node (ref "R42") (pin "1") (pintype "passive"))
      (node (ref "R43") (pin "1") (pintype "passive"))
    )
    (net (code "36") (name "Net-(Q6-B)") (class "Default")
      (node (ref "Q6") (pin "1") (pinfunction "B_1") (pintype "passive"))
      (node (ref "R77") (pin "2") (pintype "passive"))
    )
    (net (code "37") (name "Net-(Q7-B)") (class "Default")
      (node (ref "Q7") (pin "1") (pinfunction "B_1") (pintype "passive"))
      (node (ref "R72") (pin "2") (pintype "passive"))
    )
    (net (code "38") (name "Net-(Q8-B)") (class "Default")
      (node (ref "Q8") (pin "1") (pinfunction "B_1") (pintype "passive"))
      (node (ref "R69") (pin "2") (pintype "passive"))
    )
    (net (code "39") (name "Net-(Q201-B)") (class "Default")
      (node (ref "Q201") (pin "1") (pinfunction "B_1") (pintype "passive"))
      (node (ref "U203") (pin "7") (pinfunction "O_7") (pintype "passive"))
    )
    (net (code "40") (name "Net-(Q201-C)") (class "Default")
      (node (ref "C234") (pin "1") (pintype "passive"))
      (node (ref "D23") (pin "3") (pinfunction "A_3") (pintype "passive"))
      (node (ref "Q201") (pin "3") (pinfunction "C_3") (pintype "passive"))
      (node (ref "R36") (pin "2") (pintype "passive"))
      (node (ref "U10") (pin "8") (pinfunction "IOUT_8") (pintype "passive"))
      (node (ref "U203") (pin "2") (pinfunction "-_2") (pintype "passive"))
    )
    (net (code "41") (name "Net-(Q201-E)") (class "Default")
      (node (ref "Q201") (pin "2") (pinfunction "E_2") (pintype "passive"))
      (node (ref "R35") (pin "3") (pinfunction "3_3") (pintype "passive"))
    )
    (net (code "42") (name "Net-(R34-Pad2)") (class "Default")
      (node (ref "R34") (pin "2") (pintype "passive"))
      (node (ref "R35") (pin "1") (pinfunction "1_1") (pintype "passive"))
    )
    (net (code "43") (name "Net-(R55-Pad2)") (class "Default")
      (node (ref "R55") (pin "2") (pintype "passive"))
      (node (ref "R62") (pin "3") (pinfunction "3_3") (pintype "passive"))
    )
    (net (code "44") (name "Net-(R62-Pad1)") (class "Default")
      (node (ref "R62") (pin "1") (pinfunction "1_1") (pintype "passive"))
      (node (ref "R65") (pin "2") (pintype "passive"))
    )
    (net (code "45") (name "Net-(R74-Pad2)") (class "Default")
      (node (ref "R74") (pin "2") (pintype "passive"))
      (node (ref "U8") (pin "15") (pinfunction "15_15") (pintype "passive"))
    )
    (net (code "46") (name "Net-(R75-Pad2)") (class "Default")
      (node (ref "R75") (pin "2") (pintype "passive"))
      (node (ref "U8") (pin "2") (pinfunction "2_2") (pintype "passive"))
    )
    (net (code "47") (name "Net-(U10-COMP)") (class "Default")
      (node (ref "C21") (pin "1") (pintype "passive"))
      (node (ref "U10") (pin "4") (pinfunction "COMP_4") (pintype "passive"))
    )
    (net (code "48") (name "Net-(U10-VR+)") (class "Default")
      (node (ref "R38") (pin "2") (pintype "passive"))
      (node (ref "U10") (pin "2") (pinfunction "VR+_2") (pintype "passive"))
    )
    (net (code "49") (name "Net-(U10-VR-)") (class "Default")
      (node (ref "R45") (pin "1") (pintype "passive"))
      (node (ref "U10") (pin "3") (pinfunction "VR-_3") (pintype "passive"))
    )
    (net (code "50") (name "Net-(U10-~{IOUT})") (class "Default")
      (node (ref "R46") (pin "1") (pintype "passive"))
      (node (ref "U10") (pin "6") (pinfunction "~{IOUT}_6") (pintype "passive"))
    )
    (net (code "51") (name "Net-(U203A-+)") (class "Default")
      (node (ref "D28") (pin "3") (pinfunction "A_3") (pintype "passive"))
      (node (ref "R51") (pin "2") (pintype "passive"))
      (node (ref "U203") (pin "3") (pinfunction "+_3") (pintype "passive"))
    )
    (net (code "52") (name "Net-(U203B-+)") (class "Default")
      (node (ref "R39") (pin "2") (pintype "passive"))
      (node (ref "U203") (pin "5") (pinfunction "+_5") (pintype "passive"))
      (node (ref "U9") (pin "3") (pinfunction "3_3") (pintype "passive"))
    )
    (net (code "53") (name "Net-(U203B--)") (class "Default")
      (node (ref "R35") (pin "2") (pinfunction "2_2") (pintype "passive"))
      (node (ref "U203") (pin "6") (pinfunction "-_6") (pintype "passive"))
    )
    (net (code "54") (name "Net-(U206B-X2)") (class "Default")
      (node (ref "R59") (pin "2") (pintype "passive"))
      (node (ref "U206") (pin "15") (pinfunction "X2_15") (pintype "passive"))
    )
    (net (code "55") (name "Net-(U206B-Y0)") (class "Default")
      (node (ref "R60") (pin "2") (pintype "passive"))
      (node (ref "U206") (pin "1") (pinfunction "Y0_1") (pintype "passive"))
      (node (ref "U208") (pin "7") (pinfunction "O_7") (pintype "passive"))
    )
    (net (code "56") (name "Net-(U206B-Y2)") (class "Default")
      (node (ref "R58") (pin "2") (pintype "passive"))
      (node (ref "R61") (pin "1") (pintype "passive"))
      (node (ref "U206") (pin "2") (pinfunction "Y2_2") (pintype "passive"))
      (node (ref "U208") (pin "1") (pinfunction "O_1") (pintype "passive"))
    )
    (net (code "57") (name "Net-(U206C-Y)") (class "Default")
      (node (ref "R71") (pin "2") (pintype "passive"))
      (node (ref "R75") (pin "1") (pintype "passive"))
      (node (ref "U206") (pin "3") (pinfunction "Y_3") (pintype "passive"))
    )
    (net (code "58") (name "Net-(U206C-Y1)") (class "Default")
      (node (ref "R70") (pin "2") (pintype "passive"))
      (node (ref "R74") (pin "1") (pintype "passive"))
      (node (ref "U206") (pin "5") (pinfunction "Y1_5") (pintype "passive"))
    )
    (net (code "59") (name "Net-(U206C-Y3)") (class "Default")
      (node (ref "R73") (pin "2") (pintype "passive"))
      (node (ref "U206") (pin "4") (pinfunction "Y3_4") (pintype "passive"))
    )
    (net (code "60") (name "Net-(U208A--)") (class "Default")
      (node (ref "R58") (pin "1") (pintype "passive"))
      (node (ref "R62") (pin "2") (pinfunction "2_2") (pintype "passive"))
      (node (ref "R64") (pin "1") (pintype "passive"))
      (node (ref "U208") (pin "2") (pinfunction "-_2") (pintype "passive"))
    )
    (net (code "61") (name "Net-(U208B--)") (class "Default")
      (node (ref "R60") (pin "1") (pintype "passive"))
      (node (ref "R61") (pin "2") (pintype "passive"))
      (node (ref "R63") (pin "1") (pintype "passive"))
      (node (ref "U208") (pin "6") (pinfunction "-_6") (pintype "passive"))
    )
    (net (code "62") (name "Net-(U209A-+)") (class "Default")
      (node (ref "D30") (pin "3") (pinfunction "A_3") (pintype "passive"))
      (node (ref "R66") (pin "2") (pintype "passive"))
      (node (ref "U209") (pin "3") (pinfunction "+_3") (pintype "passive"))
    )
    (net (code "63") (name "Net-(U209A--)") (class "Default")
      (node (ref "R68") (pin "1") (pintype "passive"))
      (node (ref "R71") (pin "1") (pintype "passive"))
      (node (ref "U209") (pin "1") (pinfunction "O_1") (pintype "passive"))
      (node (ref "U209") (pin "2") (pinfunction "-_2") (pintype "passive"))
    )
    (net (code "64") (name "Net-(U209B--)") (class "Default")
      (node (ref "R67") (pin "1") (pintype "passive"))
      (node (ref "R68") (pin "2") (pintype "passive"))
      (node (ref "U209") (pin "6") (pinfunction "-_6") (pintype "passive"))
    )
    (net (code "65") (name "Net-(U209B-O)") (class "Default")
      (node (ref "R65") (pin "1") (pintype "passive"))
      (node (ref "R67") (pin "2") (pintype "passive"))
      (node (ref "R70") (pin "1") (pintype "passive"))
      (node (ref "U209") (pin "7") (pinfunction "O_7") (pintype "passive"))
    )
    (net (code "66") (name "P5VA") (class "Default")
      (node (ref "C10") (pin "1") (pintype "passive"))
      (node (ref "C11") (pin "1") (pintype "passive"))
      (node (ref "C24") (pin "1") (pintype "passive"))
      (node (ref "R37") (pin "1") (pintype "passive"))
      (node (ref "U206") (pin "16") (pinfunction "VCC_16") (pintype "passive"))
      (node (ref "U208") (pin "4") (pinfunction "VEE_4") (pintype "passive"))
      (node (ref "U8") (pin "12") (pinfunction "VL_12") (pintype "power_in"))
    )
    (net (code "67") (name "P5VREL") (class "Default")
      (node (ref "D31") (pin "3") (pinfunction "K_3") (pintype "passive"))
      (node (ref "D32") (pin "3") (pinfunction "K_3") (pintype "passive"))
      (node (ref "D33") (pin "3") (pinfunction "K_3") (pintype "passive"))
      (node (ref "K3") (pin "1") (pinfunction "1_1") (pintype "passive"))
      (node (ref "K4") (pin "1") (pinfunction "1_1") (pintype "passive"))
      (node (ref "K5") (pin "1") (pinfunction "1_1") (pintype "passive"))
    )
    (net (code "68") (name "P15VA") (class "Default")
      (node (ref "C12") (pin "1") (pintype "passive"))
      (node (ref "C13") (pin "1") (pintype "passive"))
      (node (ref "C14") (pin "1") (pintype "passive"))
      (node (ref "C20") (pin "2") (pintype "passive"))
      (node (ref "D23") (pin "2") (pinfunction "A_2") (pintype "passive"))
      (node (ref "D28") (pin "2") (pinfunction "A_2") (pintype "passive"))
      (node (ref "D30") (pin "2") (pinfunction "A_2") (pintype "passive"))
      (node (ref "Q2") (pin "3") (pinfunction "C_3") (pintype "passive"))
      (node (ref "R207") (pin "1") (pintype "passive"))
      (node (ref "R34") (pin "1") (pintype "passive"))
      (node (ref "U10") (pin "1") (pinfunction "VCC_1") (pintype "passive"))
      (node (ref "U203") (pin "8") (pinfunction "VCC_8") (pintype "passive"))
      (node (ref "U209") (pin "4") (pinfunction "VEE_4") (pintype "passive"))
      (node (ref "U8") (pin "13") (pinfunction "VCC_13") (pintype "power_in"))
      (node (ref "U9") (pin "1") (pinfunction "1_1") (pintype "passive"))
      (node (ref "U9") (pin "2") (pinfunction "2_2") (pintype "passive"))
    )
    (net (code "69") (name "VREF") (class "Default") (node (ref "R38") (pin "1") (pintype "passive")))
    (net (code "70") (name "unconnected-(D29-A-Pad2)") (class "Default")
      (node (ref "D29") (pin "2") (pinfunction "A_2") (pintype "passive"))
    )
    (net (code "71") (name "unconnected-(K3B-NC-Pad7)") (class "Default")
      (node (ref "K3") (pin "7") (pinfunction "NC_7") (pintype "passive"))
    )
    (net (code "72") (name "unconnected-(K4B-NC-Pad7)") (class "Default")
      (node (ref "K4") (pin "7") (pinfunction "NC_7") (pintype "passive"))
    )
  )
)
